# small_7.net
KiCad netlist of a schematic drawn in EAGLE
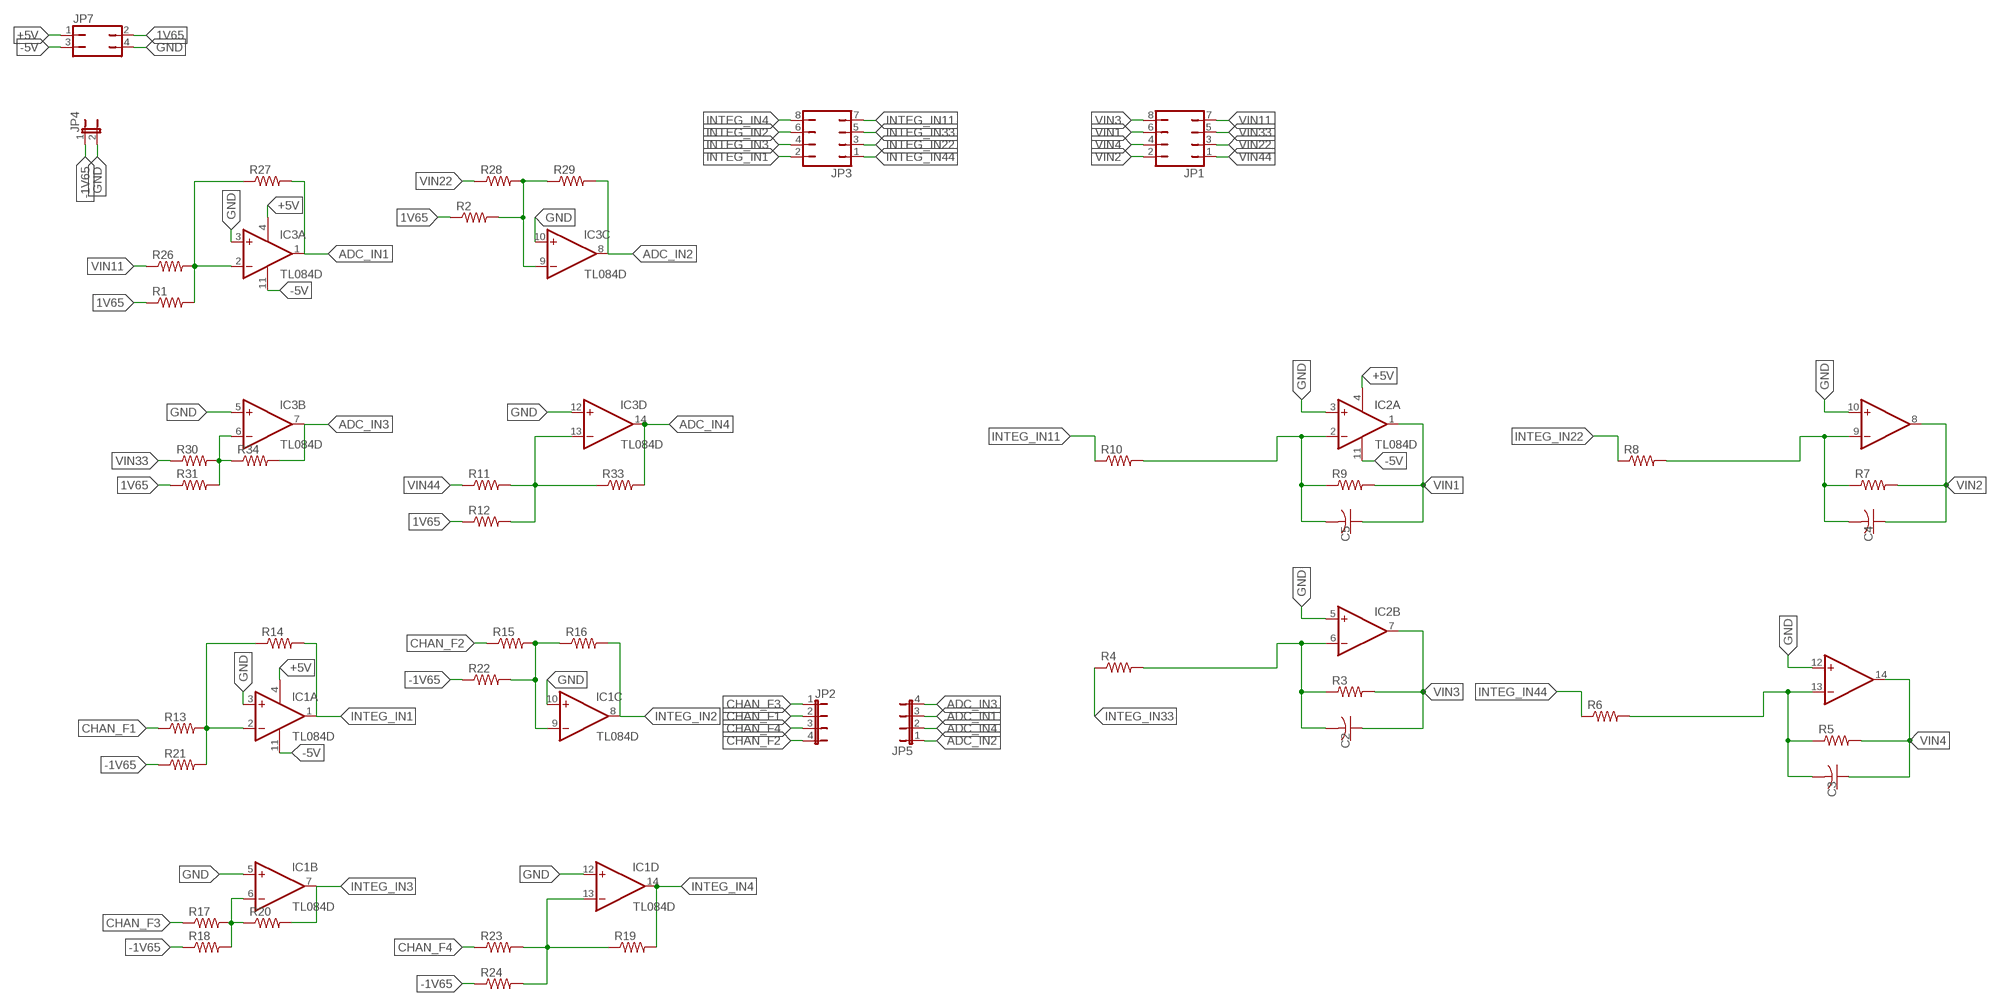
[diagram p0: schematic, sheet 1]

(export (version "E")
  (design (tool "Eeschema 10.0.6"))
  (components
    (comp (ref "C2")
      (value "C-USC1206")
      (footprint "eagle-import:C1206")
      (libsource (lib "eagle-import") (part "C-USC1206"))
    )
    (comp (ref "C3")
      (value "C-USC1206")
      (footprint "eagle-import:C1206")
      (libsource (lib "eagle-import") (part "C-USC1206"))
    )
    (comp (ref "C4")
      (value "C-USC1206")
      (footprint "eagle-import:C1206")
      (libsource (lib "eagle-import") (part "C-USC1206"))
    )
    (comp (ref "C5")
      (value "C-USC1206")
      (footprint "eagle-import:C1206")
      (libsource (lib "eagle-import") (part "C-USC1206"))
    )
    (comp (ref "IC1")
      (value "TL084D")
      (footprint "eagle-import:SO14")
      (libsource (lib "eagle-import") (part "TL084D"))
    )
    (comp (ref "IC2")
      (value "TL084D")
      (footprint "eagle-import:SO14")
      (libsource (lib "eagle-import") (part "TL084D"))
    )
    (comp (ref "IC3")
      (value "TL084D")
      (footprint "eagle-import:SO14")
      (libsource (lib "eagle-import") (part "TL084D"))
    )
    (comp (ref "JP1")
      (value "JP4Q")
      (footprint "eagle-import:JP4Q")
      (libsource (lib "eagle-import") (part "JP4Q"))
    )
    (comp (ref "JP2")
      (value "JP4E")
      (footprint "eagle-import:JP4")
      (libsource (lib "eagle-import") (part "JP4E"))
    )
    (comp (ref "JP3")
      (value "JP4Q")
      (footprint "eagle-import:JP4Q")
      (libsource (lib "eagle-import") (part "JP4Q"))
    )
    (comp (ref "JP4")
      (value "JP1E")
      (footprint "eagle-import:JP1")
      (libsource (lib "eagle-import") (part "JP1E"))
    )
    (comp (ref "JP5")
      (value "JP4E")
      (footprint "eagle-import:JP4")
      (libsource (lib "eagle-import") (part "JP4E"))
    )
    (comp (ref "JP7")
      (value "JP2Q")
      (footprint "eagle-import:JP2Q")
      (libsource (lib "eagle-import") (part "JP2Q"))
    )
    (comp (ref "R1")
      (value "R-US_R1206")
      (footprint "eagle-import:R1206")
      (libsource (lib "eagle-import") (part "R-US_R1206"))
    )
    (comp (ref "R2")
      (value "R-US_R1206")
      (footprint "eagle-import:R1206")
      (libsource (lib "eagle-import") (part "R-US_R1206"))
    )
    (comp (ref "R3")
      (value "R-US_R1206")
      (footprint "eagle-import:R1206")
      (libsource (lib "eagle-import") (part "R-US_R1206"))
    )
    (comp (ref "R4")
      (value "R-US_R1206")
      (footprint "eagle-import:R1206")
      (libsource (lib "eagle-import") (part "R-US_R1206"))
    )
    (comp (ref "R5")
      (value "R-US_R1206")
      (footprint "eagle-import:R1206")
      (libsource (lib "eagle-import") (part "R-US_R1206"))
    )
    (comp (ref "R6")
      (value "R-US_R1206")
      (footprint "eagle-import:R1206")
      (libsource (lib "eagle-import") (part "R-US_R1206"))
    )
    (comp (ref "R7")
      (value "R-US_R1206")
      (footprint "eagle-import:R1206")
      (libsource (lib "eagle-import") (part "R-US_R1206"))
    )
    (comp (ref "R8")
      (value "R-US_R1206")
      (footprint "eagle-import:R1206")
      (libsource (lib "eagle-import") (part "R-US_R1206"))
    )
    (comp (ref "R9")
      (value "R-US_R1206")
      (footprint "eagle-import:R1206")
      (libsource (lib "eagle-import") (part "R-US_R1206"))
    )
    (comp (ref "R10")
      (value "R-US_R1206")
      (footprint "eagle-import:R1206")
      (libsource (lib "eagle-import") (part "R-US_R1206"))
    )
    (comp (ref "R11")
      (value "R-US_R1206")
      (footprint "eagle-import:R1206")
      (libsource (lib "eagle-import") (part "R-US_R1206"))
    )
    (comp (ref "R12")
      (value "R-US_R1206")
      (footprint "eagle-import:R1206")
      (libsource (lib "eagle-import") (part "R-US_R1206"))
    )
    (comp (ref "R13")
      (value "R-US_R1206")
      (footprint "eagle-import:R1206")
      (libsource (lib "eagle-import") (part "R-US_R1206"))
    )
    (comp (ref "R14")
      (value "R-US_R1206")
      (footprint "eagle-import:R1206")
      (libsource (lib "eagle-import") (part "R-US_R1206"))
    )
    (comp (ref "R15")
      (value "R-US_R1206")
      (footprint "eagle-import:R1206")
      (libsource (lib "eagle-import") (part "R-US_R1206"))
    )
    (comp (ref "R16")
      (value "R-US_R1206")
      (footprint "eagle-import:R1206")
      (libsource (lib "eagle-import") (part "R-US_R1206"))
    )
    (comp (ref "R17")
      (value "R-US_R1206")
      (footprint "eagle-import:R1206")
      (libsource (lib "eagle-import") (part "R-US_R1206"))
    )
    (comp (ref "R18")
      (value "R-US_R1206")
      (footprint "eagle-import:R1206")
      (libsource (lib "eagle-import") (part "R-US_R1206"))
    )
    (comp (ref "R19")
      (value "R-US_R1206")
      (footprint "eagle-import:R1206")
      (libsource (lib "eagle-import") (part "R-US_R1206"))
    )
    (comp (ref "R20")
      (value "R-US_R1206")
      (footprint "eagle-import:R1206")
      (libsource (lib "eagle-import") (part "R-US_R1206"))
    )
    (comp (ref "R21")
      (value "R-US_R1206")
      (footprint "eagle-import:R1206")
      (libsource (lib "eagle-import") (part "R-US_R1206"))
    )
    (comp (ref "R22")
      (value "R-US_R1206")
      (footprint "eagle-import:R1206")
      (libsource (lib "eagle-import") (part "R-US_R1206"))
    )
    (comp (ref "R23")
      (value "R-US_R1206")
      (footprint "eagle-import:R1206")
      (libsource (lib "eagle-import") (part "R-US_R1206"))
    )
    (comp (ref "R24")
      (value "R-US_R1206")
      (footprint "eagle-import:R1206")
      (libsource (lib "eagle-import") (part "R-US_R1206"))
    )
    (comp (ref "R26")
      (value "R-US_R1206")
      (footprint "eagle-import:R1206")
      (libsource (lib "eagle-import") (part "R-US_R1206"))
    )
    (comp (ref "R27")
      (value "R-US_R1206")
      (footprint "eagle-import:R1206")
      (libsource (lib "eagle-import") (part "R-US_R1206"))
    )
    (comp (ref "R28")
      (value "R-US_R1206")
      (footprint "eagle-import:R1206")
      (libsource (lib "eagle-import") (part "R-US_R1206"))
    )
    (comp (ref "R29")
      (value "R-US_R1206")
      (footprint "eagle-import:R1206")
      (libsource (lib "eagle-import") (part "R-US_R1206"))
    )
    (comp (ref "R30")
      (value "R-US_R1206")
      (footprint "eagle-import:R1206")
      (libsource (lib "eagle-import") (part "R-US_R1206"))
    )
    (comp (ref "R31")
      (value "R-US_R1206")
      (footprint "eagle-import:R1206")
      (libsource (lib "eagle-import") (part "R-US_R1206"))
    )
    (comp (ref "R33")
      (value "R-US_R1206")
      (footprint "eagle-import:R1206")
      (libsource (lib "eagle-import") (part "R-US_R1206"))
    )
    (comp (ref "R34")
      (value "R-US_R1206")
      (footprint "eagle-import:R1206")
      (libsource (lib "eagle-import") (part "R-US_R1206"))
    )
  )
  (nets
    (net (code "1") (name "+5V") (class "Default")
      (node (ref "IC1") (pin "4") (pinfunction "V+_4") (pintype "power_in"))
      (node (ref "IC2") (pin "4") (pinfunction "V+_4") (pintype "power_in"))
      (node (ref "IC3") (pin "4") (pinfunction "V+_4") (pintype "power_in"))
      (node (ref "JP7") (pin "1") (pinfunction "1_1") (pintype "passive"))
    )
    (net (code "2") (name "-1V65") (class "Default")
      (node (ref "JP4") (pin "1") (pinfunction "1_1") (pintype "passive"))
      (node (ref "R18") (pin "1") (pinfunction "1_1") (pintype "passive"))
      (node (ref "R21") (pin "1") (pinfunction "1_1") (pintype "passive"))
      (node (ref "R22") (pin "1") (pinfunction "1_1") (pintype "passive"))
      (node (ref "R24") (pin "1") (pinfunction "1_1") (pintype "passive"))
    )
    (net (code "3") (name "-5V") (class "Default")
      (node (ref "IC1") (pin "11") (pinfunction "V-_11") (pintype "power_in"))
      (node (ref "IC2") (pin "11") (pinfunction "V-_11") (pintype "power_in"))
      (node (ref "IC3") (pin "11") (pinfunction "V-_11") (pintype "power_in"))
      (node (ref "JP7") (pin "3") (pinfunction "3_3") (pintype "passive"))
    )
    (net (code "4") (name "1V65") (class "Default")
      (node (ref "JP7") (pin "2") (pinfunction "2_2") (pintype "passive"))
      (node (ref "R1") (pin "1") (pinfunction "1_1") (pintype "passive"))
      (node (ref "R12") (pin "1") (pinfunction "1_1") (pintype "passive"))
      (node (ref "R2") (pin "1") (pinfunction "1_1") (pintype "passive"))
      (node (ref "R31") (pin "1") (pinfunction "1_1") (pintype "passive"))
    )
    (net (code "5") (name "ADC_IN1") (class "Default")
      (node (ref "IC3") (pin "1") (pinfunction "OUT_1") (pintype "output"))
      (node (ref "JP5") (pin "3") (pinfunction "3_3") (pintype "passive"))
      (node (ref "R27") (pin "2") (pinfunction "2_2") (pintype "passive"))
    )
    (net (code "6") (name "ADC_IN2") (class "Default")
      (node (ref "IC3") (pin "8") (pinfunction "OUT_8") (pintype "output"))
      (node (ref "JP5") (pin "1") (pinfunction "1_1") (pintype "passive"))
      (node (ref "R29") (pin "2") (pinfunction "2_2") (pintype "passive"))
    )
    (net (code "7") (name "ADC_IN3") (class "Default")
      (node (ref "IC3") (pin "7") (pinfunction "OUT_7") (pintype "output"))
      (node (ref "JP5") (pin "4") (pinfunction "4_4") (pintype "passive"))
      (node (ref "R34") (pin "2") (pinfunction "2_2") (pintype "passive"))
    )
    (net (code "8") (name "ADC_IN4") (class "Default")
      (node (ref "IC3") (pin "14") (pinfunction "OUT_14") (pintype "output"))
      (node (ref "JP5") (pin "2") (pinfunction "2_2") (pintype "passive"))
      (node (ref "R33") (pin "2") (pinfunction "2_2") (pintype "passive"))
    )
    (net (code "9") (name "CHAN_F1") (class "Default")
      (node (ref "JP2") (pin "2") (pinfunction "2_2") (pintype "passive"))
      (node (ref "R13") (pin "1") (pinfunction "1_1") (pintype "passive"))
    )
    (net (code "10") (name "CHAN_F2") (class "Default")
      (node (ref "JP2") (pin "4") (pinfunction "4_4") (pintype "passive"))
      (node (ref "R15") (pin "1") (pinfunction "1_1") (pintype "passive"))
    )
    (net (code "11") (name "CHAN_F3") (class "Default")
      (node (ref "JP2") (pin "1") (pinfunction "1_1") (pintype "passive"))
      (node (ref "R17") (pin "1") (pinfunction "1_1") (pintype "passive"))
    )
    (net (code "12") (name "CHAN_F4") (class "Default")
      (node (ref "JP2") (pin "3") (pinfunction "3_3") (pintype "passive"))
      (node (ref "R23") (pin "1") (pinfunction "1_1") (pintype "passive"))
    )
    (net (code "13") (name "GND") (class "Default")
      (node (ref "IC1") (pin "10") (pinfunction "+IN_10") (pintype "input"))
      (node (ref "IC1") (pin "12") (pinfunction "+IN_12") (pintype "input"))
      (node (ref "IC1") (pin "3") (pinfunction "+IN_3") (pintype "input"))
      (node (ref "IC1") (pin "5") (pinfunction "+IN_5") (pintype "input"))
      (node (ref "IC2") (pin "10") (pinfunction "+IN_10") (pintype "input"))
      (node (ref "IC2") (pin "12") (pinfunction "+IN_12") (pintype "input"))
      (node (ref "IC2") (pin "3") (pinfunction "+IN_3") (pintype "input"))
      (node (ref "IC2") (pin "5") (pinfunction "+IN_5") (pintype "input"))
      (node (ref "IC3") (pin "10") (pinfunction "+IN_10") (pintype "input"))
      (node (ref "IC3") (pin "12") (pinfunction "+IN_12") (pintype "input"))
      (node (ref "IC3") (pin "3") (pinfunction "+IN_3") (pintype "input"))
      (node (ref "IC3") (pin "5") (pinfunction "+IN_5") (pintype "input"))
      (node (ref "JP4") (pin "2") (pinfunction "2_2") (pintype "passive"))
      (node (ref "JP7") (pin "4") (pinfunction "4_4") (pintype "passive"))
    )
    (net (code "14") (name "INTEG_IN1") (class "Default")
      (node (ref "IC1") (pin "1") (pinfunction "OUT_1") (pintype "output"))
      (node (ref "JP3") (pin "2") (pinfunction "2_2") (pintype "passive"))
      (node (ref "R14") (pin "2") (pinfunction "2_2") (pintype "passive"))
    )
    (net (code "15") (name "INTEG_IN2") (class "Default")
      (node (ref "IC1") (pin "8") (pinfunction "OUT_8") (pintype "output"))
      (node (ref "JP3") (pin "6") (pinfunction "6_6") (pintype "passive"))
      (node (ref "R16") (pin "2") (pinfunction "2_2") (pintype "passive"))
    )
    (net (code "16") (name "INTEG_IN3") (class "Default")
      (node (ref "IC1") (pin "7") (pinfunction "OUT_7") (pintype "output"))
      (node (ref "JP3") (pin "4") (pinfunction "4_4") (pintype "passive"))
      (node (ref "R20") (pin "2") (pinfunction "2_2") (pintype "passive"))
    )
    (net (code "17") (name "INTEG_IN4") (class "Default")
      (node (ref "IC1") (pin "14") (pinfunction "OUT_14") (pintype "output"))
      (node (ref "JP3") (pin "8") (pinfunction "8_8") (pintype "passive"))
      (node (ref "R19") (pin "2") (pinfunction "2_2") (pintype "passive"))
    )
    (net (code "18") (name "INTEG_IN11") (class "Default")
      (node (ref "JP3") (pin "7") (pinfunction "7_7") (pintype "passive"))
      (node (ref "R10") (pin "1") (pinfunction "1_1") (pintype "passive"))
    )
    (net (code "19") (name "INTEG_IN22") (class "Default")
      (node (ref "JP3") (pin "3") (pinfunction "3_3") (pintype "passive"))
      (node (ref "R8") (pin "1") (pinfunction "1_1") (pintype "passive"))
    )
    (net (code "20") (name "INTEG_IN33") (class "Default")
      (node (ref "JP3") (pin "5") (pinfunction "5_5") (pintype "passive"))
      (node (ref "R4") (pin "1") (pinfunction "1_1") (pintype "passive"))
    )
    (net (code "21") (name "INTEG_IN44") (class "Default")
      (node (ref "JP3") (pin "1") (pinfunction "1_1") (pintype "passive"))
      (node (ref "R6") (pin "1") (pinfunction "1_1") (pintype "passive"))
    )
    (net (code "22") (name "Net-(IC1A--IN)") (class "Default")
      (node (ref "IC1") (pin "2") (pinfunction "-IN_2") (pintype "input"))
      (node (ref "R13") (pin "2") (pinfunction "2_2") (pintype "passive"))
      (node (ref "R14") (pin "1") (pinfunction "1_1") (pintype "passive"))
      (node (ref "R21") (pin "2") (pinfunction "2_2") (pintype "passive"))
    )
    (net (code "23") (name "Net-(IC1B--IN)") (class "Default")
      (node (ref "IC1") (pin "6") (pinfunction "-IN_6") (pintype "input"))
      (node (ref "R17") (pin "2") (pinfunction "2_2") (pintype "passive"))
      (node (ref "R18") (pin "2") (pinfunction "2_2") (pintype "passive"))
      (node (ref "R20") (pin "1") (pinfunction "1_1") (pintype "passive"))
    )
    (net (code "24") (name "Net-(IC1C--IN)") (class "Default")
      (node (ref "IC1") (pin "9") (pinfunction "-IN_9") (pintype "input"))
      (node (ref "R15") (pin "2") (pinfunction "2_2") (pintype "passive"))
      (node (ref "R16") (pin "1") (pinfunction "1_1") (pintype "passive"))
      (node (ref "R22") (pin "2") (pinfunction "2_2") (pintype "passive"))
    )
    (net (code "25") (name "Net-(IC1D--IN)") (class "Default")
      (node (ref "IC1") (pin "13") (pinfunction "-IN_13") (pintype "input"))
      (node (ref "R19") (pin "1") (pinfunction "1_1") (pintype "passive"))
      (node (ref "R23") (pin "2") (pinfunction "2_2") (pintype "passive"))
      (node (ref "R24") (pin "2") (pinfunction "2_2") (pintype "passive"))
    )
    (net (code "26") (name "Net-(IC2A--IN)") (class "Default")
      (node (ref "C5") (pin "2") (pinfunction "2_2") (pintype "passive"))
      (node (ref "IC2") (pin "2") (pinfunction "-IN_2") (pintype "input"))
      (node (ref "R10") (pin "2") (pinfunction "2_2") (pintype "passive"))
      (node (ref "R9") (pin "1") (pinfunction "1_1") (pintype "passive"))
    )
    (net (code "27") (name "Net-(IC2B--IN)") (class "Default")
      (node (ref "C2") (pin "2") (pinfunction "2_2") (pintype "passive"))
      (node (ref "IC2") (pin "6") (pinfunction "-IN_6") (pintype "input"))
      (node (ref "R3") (pin "1") (pinfunction "1_1") (pintype "passive"))
      (node (ref "R4") (pin "2") (pinfunction "2_2") (pintype "passive"))
    )
    (net (code "28") (name "Net-(IC2C--IN)") (class "Default")
      (node (ref "C4") (pin "2") (pinfunction "2_2") (pintype "passive"))
      (node (ref "IC2") (pin "9") (pinfunction "-IN_9") (pintype "input"))
      (node (ref "R7") (pin "1") (pinfunction "1_1") (pintype "passive"))
      (node (ref "R8") (pin "2") (pinfunction "2_2") (pintype "passive"))
    )
    (net (code "29") (name "Net-(IC2D--IN)") (class "Default")
      (node (ref "C3") (pin "2") (pinfunction "2_2") (pintype "passive"))
      (node (ref "IC2") (pin "13") (pinfunction "-IN_13") (pintype "input"))
      (node (ref "R5") (pin "1") (pinfunction "1_1") (pintype "passive"))
      (node (ref "R6") (pin "2") (pinfunction "2_2") (pintype "passive"))
    )
    (net (code "30") (name "Net-(IC3A--IN)") (class "Default")
      (node (ref "IC3") (pin "2") (pinfunction "-IN_2") (pintype "input"))
      (node (ref "R1") (pin "2") (pinfunction "2_2") (pintype "passive"))
      (node (ref "R26") (pin "2") (pinfunction "2_2") (pintype "passive"))
      (node (ref "R27") (pin "1") (pinfunction "1_1") (pintype "passive"))
    )
    (net (code "31") (name "Net-(IC3B--IN)") (class "Default")
      (node (ref "IC3") (pin "6") (pinfunction "-IN_6") (pintype "input"))
      (node (ref "R30") (pin "2") (pinfunction "2_2") (pintype "passive"))
      (node (ref "R31") (pin "2") (pinfunction "2_2") (pintype "passive"))
      (node (ref "R34") (pin "1") (pinfunction "1_1") (pintype "passive"))
    )
    (net (code "32") (name "Net-(IC3C--IN)") (class "Default")
      (node (ref "IC3") (pin "9") (pinfunction "-IN_9") (pintype "input"))
      (node (ref "R2") (pin "2") (pinfunction "2_2") (pintype "passive"))
      (node (ref "R28") (pin "2") (pinfunction "2_2") (pintype "passive"))
      (node (ref "R29") (pin "1") (pinfunction "1_1") (pintype "passive"))
    )
    (net (code "33") (name "Net-(IC3D--IN)") (class "Default")
      (node (ref "IC3") (pin "13") (pinfunction "-IN_13") (pintype "input"))
      (node (ref "R11") (pin "2") (pinfunction "2_2") (pintype "passive"))
      (node (ref "R12") (pin "2") (pinfunction "2_2") (pintype "passive"))
      (node (ref "R33") (pin "1") (pinfunction "1_1") (pintype "passive"))
    )
    (net (code "34") (name "VIN1") (class "Default")
      (node (ref "C5") (pin "1") (pinfunction "1_1") (pintype "passive"))
      (node (ref "IC2") (pin "1") (pinfunction "OUT_1") (pintype "output"))
      (node (ref "JP1") (pin "6") (pinfunction "6_6") (pintype "passive"))
      (node (ref "R9") (pin "2") (pinfunction "2_2") (pintype "passive"))
    )
    (net (code "35") (name "VIN2") (class "Default")
      (node (ref "C4") (pin "1") (pinfunction "1_1") (pintype "passive"))
      (node (ref "IC2") (pin "8") (pinfunction "OUT_8") (pintype "output"))
      (node (ref "JP1") (pin "2") (pinfunction "2_2") (pintype "passive"))
      (node (ref "R7") (pin "2") (pinfunction "2_2") (pintype "passive"))
    )
    (net (code "36") (name "VIN3") (class "Default")
      (node (ref "C2") (pin "1") (pinfunction "1_1") (pintype "passive"))
      (node (ref "IC2") (pin "7") (pinfunction "OUT_7") (pintype "output"))
      (node (ref "JP1") (pin "8") (pinfunction "8_8") (pintype "passive"))
      (node (ref "R3") (pin "2") (pinfunction "2_2") (pintype "passive"))
    )
    (net (code "37") (name "VIN4") (class "Default")
      (node (ref "C3") (pin "1") (pinfunction "1_1") (pintype "passive"))
      (node (ref "IC2") (pin "14") (pinfunction "OUT_14") (pintype "output"))
      (node (ref "JP1") (pin "4") (pinfunction "4_4") (pintype "passive"))
      (node (ref "R5") (pin "2") (pinfunction "2_2") (pintype "passive"))
    )
    (net (code "38") (name "VIN11") (class "Default")
      (node (ref "JP1") (pin "7") (pinfunction "7_7") (pintype "passive"))
      (node (ref "R26") (pin "1") (pinfunction "1_1") (pintype "passive"))
    )
    (net (code "39") (name "VIN22") (class "Default")
      (node (ref "JP1") (pin "3") (pinfunction "3_3") (pintype "passive"))
      (node (ref "R28") (pin "1") (pinfunction "1_1") (pintype "passive"))
    )
    (net (code "40") (name "VIN33") (class "Default")
      (node (ref "JP1") (pin "5") (pinfunction "5_5") (pintype "passive"))
      (node (ref "R30") (pin "1") (pinfunction "1_1") (pintype "passive"))
    )
    (net (code "41") (name "VIN44") (class "Default")
      (node (ref "JP1") (pin "1") (pinfunction "1_1") (pintype "passive"))
      (node (ref "R11") (pin "1") (pinfunction "1_1") (pintype "passive"))
    )
  )
)
